# AC_Dimmer.net
KiCad netlist of a schematic drawn in Altium Designer
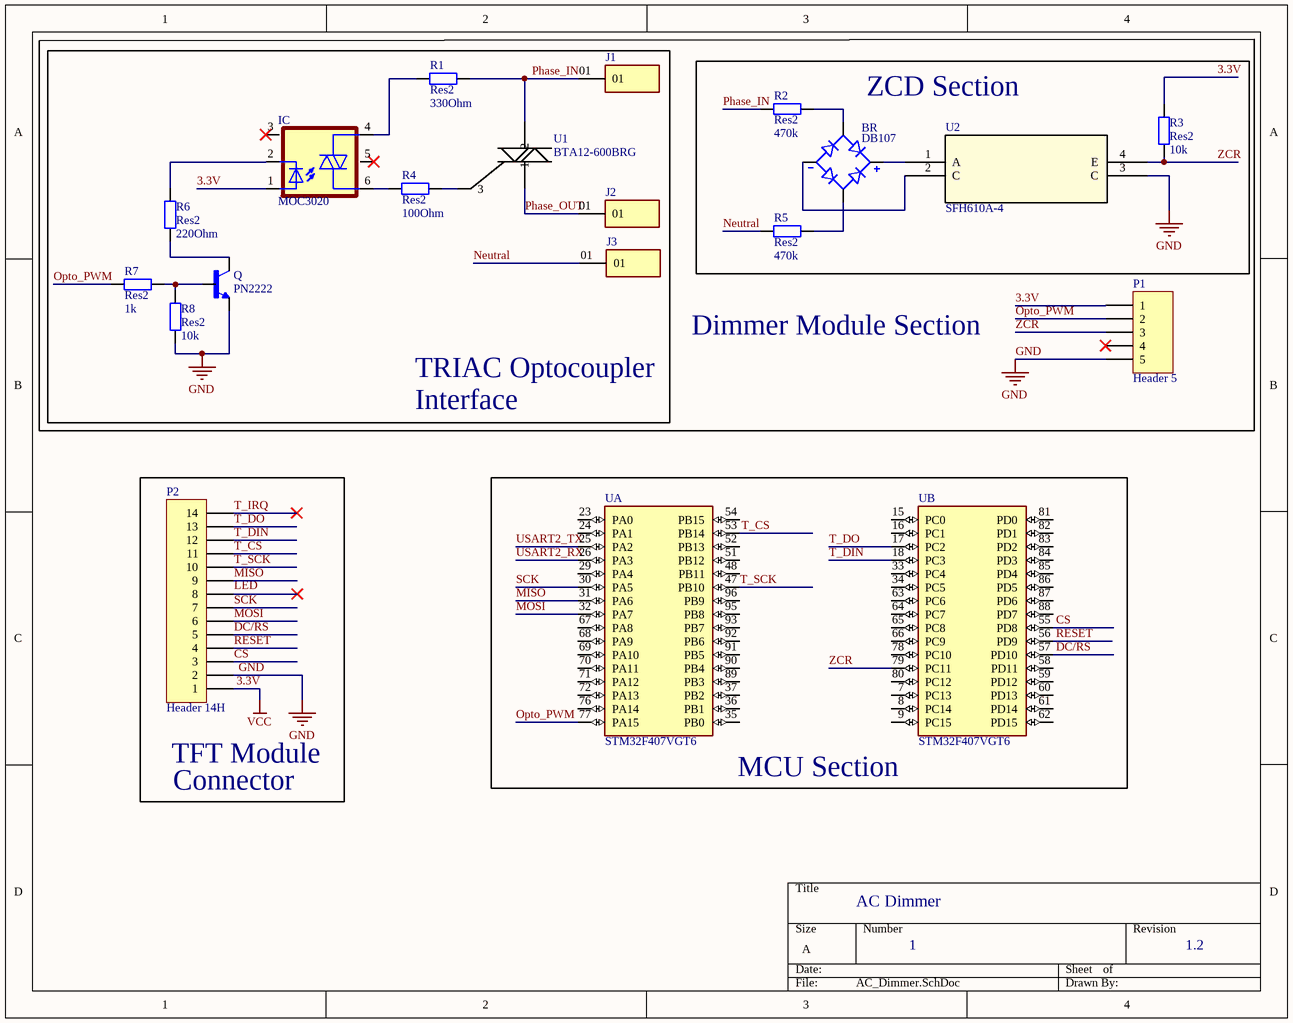
[diagram p0: AC_Dimmer.SchDoc]

(export (version "E")
  (design (tool "Eeschema 10.0.6"))
  (components
    (comp (ref "BR")
      (value "DB107")
      (footprint "DIP825W50P509L880H320Q4")
      (description "Bridge Rectifier Single Phase Standard 1kV Surface Mount DB-S")
      (fields (field (name "MF") "EIC Semiconductor"))
      (libsource (lib "DB107") (part "DB107"))
    )
    (comp (ref "IC")
      (value "MOC3020")
      (footprint "DIL06-A")
      (description "Optoisolator Triac Output 5300Vrms 1 Channel 6-DIP")
      (fields (field (name "MF") "ON Semiconductor"))
      (libsource (lib "MOC3020") (part "MOC3020"))
    )
    (comp (ref "J1")
      (value "MTMM-101-07-T-S-230")
      (footprint "SAMTEC_MTMM-101-07-T-S-230")
      (libsource (lib "MTMM-101-07-T-S-230") (part "MTMM-101-07-T-S-230"))
    )
    (comp (ref "J2")
      (value "MTMM-101-07-T-S-230")
      (footprint "SAMTEC_MTMM-101-07-T-S-230")
      (libsource (lib "MTMM-101-07-T-S-230") (part "MTMM-101-07-T-S-230"))
    )
    (comp (ref "J3")
      (value "MTMM-101-07-T-S-230")
      (footprint "SAMTEC_MTMM-101-07-T-S-230")
      (libsource (lib "MTMM-101-07-T-S-230") (part "MTMM-101-07-T-S-230"))
    )
    (comp (ref "P1")
      (value "Header 5")
      (footprint "HDR1X5")
      (description "Header, 5-Pin")
      (fields (field (name "PUBLISHER") "Altium Limited"))
      (libsource (lib "Miscellaneous Connectors") (part "Header 5"))
    )
    (comp (ref "P2")
      (value "Header 14H")
      (footprint "HDR1X14H")
      (description "Header, 14-Pin, Right Angle")
      (fields (field (name "PUBLISHER") "Altium Limited"))
      (libsource (lib "Miscellaneous Connectors") (part "Header 14H"))
    )
    (comp (ref "Q")
      (value "PN2222")
      (footprint "TO92")
      (description "Bipolar (BJT) Transistor NPN 40V 1A 300MHz 625mW Through Hole TO-92-3")
      (fields (field (name "MF") "ON Semiconductor"))
      (libsource (lib "PN2222") (part "PN2222"))
    )
    (comp (ref "R1")
      (value "Res2")
      (footprint "AXIAL-0.4")
      (description "Resistor")
      (fields (field (name "ALTIUM_VALUE") "330Ohm") (field (name "PUBLISHER") "Altium Limited"))
      (libsource (lib "") (part "Res2_1"))
    )
    (comp (ref "R2")
      (value "Res2")
      (footprint "AXIAL-0.4")
      (description "Resistor")
      (fields (field (name "ALTIUM_VALUE") "470k") (field (name "PUBLISHER") "Altium Limited"))
      (libsource (lib "") (part "Res2_2"))
    )
    (comp (ref "R3")
      (value "Res2")
      (footprint "AXIAL-0.4")
      (description "Resistor")
      (fields (field (name "ALTIUM_VALUE") "10k") (field (name "PUBLISHER") "Altium Limited"))
      (libsource (lib "Miscellaneous Devices") (part "Res2"))
    )
    (comp (ref "R4")
      (value "Res2")
      (footprint "AXIAL-0.4")
      (description "Resistor")
      (fields (field (name "ALTIUM_VALUE") "100Ohm") (field (name "PUBLISHER") "Altium Limited"))
      (libsource (lib "") (part "Res2_1"))
    )
    (comp (ref "R5")
      (value "Res2")
      (footprint "AXIAL-0.4")
      (description "Resistor")
      (fields (field (name "ALTIUM_VALUE") "470k") (field (name "PUBLISHER") "Altium Limited"))
      (libsource (lib "") (part "Res2_2"))
    )
    (comp (ref "R6")
      (value "Res2")
      (footprint "AXIAL-0.4")
      (description "Resistor")
      (fields (field (name "ALTIUM_VALUE") "220Ohm") (field (name "PUBLISHER") "Altium Limited"))
      (libsource (lib "Miscellaneous Devices") (part "Res2"))
    )
    (comp (ref "R7")
      (value "Res2")
      (footprint "AXIAL-0.4")
      (description "Resistor")
      (fields (field (name "ALTIUM_VALUE") "1k") (field (name "PUBLISHER") "Altium Limited"))
      (libsource (lib "") (part "Res2_1"))
    )
    (comp (ref "R8")
      (value "Res2")
      (footprint "AXIAL-0.4")
      (description "Resistor")
      (fields (field (name "ALTIUM_VALUE") "10k") (field (name "PUBLISHER") "Altium Limited"))
      (libsource (lib "Miscellaneous Devices") (part "Res2"))
    )
    (comp (ref "U")
      (value "STM32F407VGT6")
      (footprint "QFP50P1600X1600X160-100N")
      (description "ARMÂ® CortexÂ®-M4 STM32F4 Microcontroller IC 32-Bit 168MHz 1MB _1M x 8_ FLASH 100-LQFP _14x14_")
      (fields (field (name "MF") "STMicroelectronics"))
      (libsource (lib "STM32F407VGT6") (part "STM32F407VGT6"))
    )
    (comp (ref "U1")
      (value "BTA12-600BRG")
      (footprint "TO-220AB_STM")
      (description "No Description Available")
      (fields (field (name "COPYRIGHT") "Copyright (C) 2022 Ultra Librarian. All rights reserved."))
      (libsource (lib "BTA12-600BRG") (part "BTA12-600BRG"))
    )
    (comp (ref "U2")
      (value "SFH610A-4")
      (footprint "DIP-4_SFH610A_VIS")
      (description "No Description Available")
      (fields (field (name "COPYRIGHT") "Copyright (C) 2022 Ultra Librarian. All rights reserved."))
      (libsource (lib "SFH610A-4") (part "SFH610A-4"))
    )
  )
  (nets
    (net (code "1") (name "/CS") (class "Default")
      (node (ref "P2") (pin "3") (pinfunction "3_3") (pintype "passive"))
      (node (ref "U") (pin "55") (pinfunction "PD8_55") (pintype "bidirectional"))
    )
    (net (code "2") (name "/DC{slash}RS") (class "Default")
      (node (ref "P2") (pin "5") (pinfunction "5_5") (pintype "passive"))
      (node (ref "U") (pin "57") (pinfunction "PD10_57") (pintype "bidirectional"))
    )
    (net (code "4") (name "/MISO") (class "Default")
      (node (ref "P2") (pin "9") (pinfunction "9_9") (pintype "passive"))
      (node (ref "U") (pin "31") (pinfunction "PA6_31") (pintype "bidirectional"))
    )
    (net (code "5") (name "/MOSI") (class "Default")
      (node (ref "P2") (pin "6") (pinfunction "6_6") (pintype "passive"))
      (node (ref "U") (pin "32") (pinfunction "PA7_32") (pintype "bidirectional"))
    )
    (net (code "6") (name "/Neutral") (class "Default")
      (node (ref "J3") (pin "01") (pinfunction "01_01") (pintype "passive"))
      (node (ref "R5") (pin "1") (pinfunction "1_1") (pintype "passive"))
    )
    (net (code "7") (name "/Opto_PWM") (class "Default")
      (node (ref "P1") (pin "2") (pinfunction "2_2") (pintype "passive"))
      (node (ref "R7") (pin "2") (pinfunction "2_2") (pintype "passive"))
      (node (ref "U") (pin "77") (pinfunction "PA15_77") (pintype "bidirectional"))
    )
    (net (code "8") (name "/Phase_IN") (class "Default")
      (node (ref "J1") (pin "01") (pinfunction "01_01") (pintype "passive"))
      (node (ref "R1") (pin "1") (pinfunction "1_1") (pintype "passive"))
      (node (ref "R2") (pin "1") (pinfunction "1_1") (pintype "passive"))
      (node (ref "U1") (pin "2") (pinfunction "2_2") (pintype "passive"))
    )
    (net (code "9") (name "/Phase_OUT") (class "Default")
      (node (ref "J2") (pin "01") (pinfunction "01_01") (pintype "passive"))
      (node (ref "U1") (pin "1") (pinfunction "1_1") (pintype "passive"))
    )
    (net (code "10") (name "/RESET") (class "Default")
      (node (ref "P2") (pin "4") (pinfunction "4_4") (pintype "passive"))
      (node (ref "U") (pin "56") (pinfunction "PD9_56") (pintype "bidirectional"))
    )
    (net (code "11") (name "/SCK") (class "Default")
      (node (ref "P2") (pin "7") (pinfunction "7_7") (pintype "passive"))
      (node (ref "U") (pin "30") (pinfunction "PA5_30") (pintype "bidirectional"))
    )
    (net (code "12") (name "/T_CS") (class "Default")
      (node (ref "P2") (pin "11") (pinfunction "11_11") (pintype "passive"))
      (node (ref "U") (pin "53") (pinfunction "PB14_53") (pintype "bidirectional"))
    )
    (net (code "13") (name "/T_DIN") (class "Default")
      (node (ref "P2") (pin "12") (pinfunction "12_12") (pintype "passive"))
      (node (ref "U") (pin "18") (pinfunction "PC3_18") (pintype "bidirectional"))
    )
    (net (code "14") (name "/T_DO") (class "Default")
      (node (ref "P2") (pin "13") (pinfunction "13_13") (pintype "passive"))
      (node (ref "U") (pin "17") (pinfunction "PC2_17") (pintype "bidirectional"))
    )
    (net (code "15") (name "/T_IRQ") (class "Default")
      (node (ref "P2") (pin "14") (pinfunction "14_14") (pintype "passive+no_connect"))
    )
    (net (code "16") (name "/T_SCK") (class "Default")
      (node (ref "P2") (pin "10") (pinfunction "10_10") (pintype "passive"))
      (node (ref "U") (pin "47") (pinfunction "PB10_47") (pintype "bidirectional"))
    )
    (net (code "17") (name "/USART2_RX") (class "Default")
      (node (ref "U") (pin "26") (pinfunction "PA3_26") (pintype "bidirectional"))
    )
    (net (code "18") (name "/USART2_TX") (class "Default")
      (node (ref "U") (pin "25") (pinfunction "PA2_25") (pintype "bidirectional"))
    )
    (net (code "19") (name "/ZCR") (class "Default")
      (node (ref "P1") (pin "3") (pinfunction "3_3") (pintype "passive"))
      (node (ref "R3") (pin "2") (pinfunction "2_2") (pintype "passive"))
      (node (ref "U") (pin "79") (pinfunction "PC11_79") (pintype "bidirectional"))
      (node (ref "U2") (pin "4") (pinfunction "E_4") (pintype "passive"))
    )
    (net (code "20") (name "GND") (class "Default")
      (node (ref "P1") (pin "5") (pinfunction "5_5") (pintype "passive"))
      (node (ref "P2") (pin "2") (pinfunction "2_2") (pintype "passive"))
      (node (ref "Q") (pin "1") (pinfunction "E_1") (pintype "passive"))
      (node (ref "R8") (pin "2") (pinfunction "2_2") (pintype "passive"))
      (node (ref "U2") (pin "3") (pinfunction "C_3") (pintype "passive"))
    )
    (net (code "21") (name "Net-(BR-AC1)") (class "Default")
      (node (ref "BR") (pin "3") (pinfunction "AC1_3") (pintype "passive"))
      (node (ref "R5") (pin "2") (pinfunction "2_2") (pintype "passive"))
    )
    (net (code "22") (name "Net-(BR-AC2)") (class "Default")
      (node (ref "BR") (pin "4") (pinfunction "AC2_4") (pintype "passive"))
      (node (ref "R2") (pin "2") (pinfunction "2_2") (pintype "passive"))
    )
    (net (code "23") (name "Net-(BR-NEG)") (class "Default")
      (node (ref "BR") (pin "2") (pinfunction "NEG_2") (pintype "passive"))
      (node (ref "U2") (pin "2") (pinfunction "C_2") (pintype "passive"))
    )
    (net (code "24") (name "Net-(BR-POS)") (class "Default")
      (node (ref "BR") (pin "1") (pinfunction "POS_1") (pintype "passive"))
      (node (ref "U2") (pin "1") (pinfunction "A_1") (pintype "passive"))
    )
    (net (code "25") (name "Net-(IC-A1)") (class "Default")
      (node (ref "IC") (pin "4") (pinfunction "A1_4") (pintype "passive"))
      (node (ref "R1") (pin "2") (pinfunction "2_2") (pintype "passive"))
    )
    (net (code "26") (name "Net-(IC-A2)") (class "Default")
      (node (ref "IC") (pin "6") (pinfunction "A2_6") (pintype "passive"))
      (node (ref "R4") (pin "2") (pinfunction "2_2") (pintype "passive"))
    )
    (net (code "27") (name "Net-(IC-C)") (class "Default")
      (node (ref "IC") (pin "2") (pinfunction "C_2") (pintype "passive"))
      (node (ref "R6") (pin "1") (pinfunction "1_1") (pintype "passive"))
    )
    (net (code "28") (name "Net-(Q-B)") (class "Default")
      (node (ref "Q") (pin "2") (pinfunction "B_2") (pintype "passive"))
      (node (ref "R7") (pin "1") (pinfunction "1_1") (pintype "passive"))
      (node (ref "R8") (pin "1") (pinfunction "1_1") (pintype "passive"))
    )
    (net (code "29") (name "Net-(Q-C)") (class "Default")
      (node (ref "Q") (pin "3") (pinfunction "C_3") (pintype "passive"))
      (node (ref "R6") (pin "2") (pinfunction "2_2") (pintype "passive"))
    )
    (net (code "30") (name "Net-(R4-Pad1)") (class "Default")
      (node (ref "R4") (pin "1") (pinfunction "1_1") (pintype "passive"))
      (node (ref "U1") (pin "3") (pinfunction "3_3") (pintype "passive"))
    )
    (net (code "31") (name "VCC") (class "Default")
      (node (ref "IC") (pin "1") (pinfunction "A_1") (pintype "passive"))
      (node (ref "P1") (pin "1") (pinfunction "1_1") (pintype "passive"))
      (node (ref "P2") (pin "1") (pinfunction "1_1") (pintype "passive"))
      (node (ref "R3") (pin "1") (pinfunction "1_1") (pintype "passive"))
    )
    (net (code "32") (name "unconnected-(IC-P$1-Pad3)") (class "Default")
      (node (ref "IC") (pin "3") (pinfunction "P$1_3") (pintype "open_collector+no_connect"))
    )
    (net (code "33") (name "unconnected-(IC-P$2-Pad5)") (class "Default")
      (node (ref "IC") (pin "5") (pinfunction "P$2_5") (pintype "open_collector+no_connect"))
    )
    (net (code "34") (name "unconnected-(P1-Pad4)") (class "Default")
      (node (ref "P1") (pin "4") (pinfunction "4_4") (pintype "passive+no_connect"))
    )
    (net (code "35") (name "unconnected-(P2-Pad8)") (class "Default")
      (node (ref "P2") (pin "8") (pinfunction "8_8") (pintype "passive+no_connect"))
    )
    (net (code "36") (name "unconnected-(UA-PA0-Pad23)") (class "Default")
      (node (ref "U") (pin "23") (pinfunction "PA0_23") (pintype "bidirectional"))
    )
    (net (code "37") (name "unconnected-(UA-PA1-Pad24)") (class "Default")
      (node (ref "U") (pin "24") (pinfunction "PA1_24") (pintype "bidirectional"))
    )
    (net (code "38") (name "unconnected-(UA-PA4-Pad29)") (class "Default")
      (node (ref "U") (pin "29") (pinfunction "PA4_29") (pintype "bidirectional"))
    )
    (net (code "39") (name "unconnected-(UA-PA8-Pad67)") (class "Default")
      (node (ref "U") (pin "67") (pinfunction "PA8_67") (pintype "bidirectional"))
    )
    (net (code "40") (name "unconnected-(UA-PA9-Pad68)") (class "Default")
      (node (ref "U") (pin "68") (pinfunction "PA9_68") (pintype "bidirectional"))
    )
    (net (code "41") (name "unconnected-(UA-PA10-Pad69)") (class "Default")
      (node (ref "U") (pin "69") (pinfunction "PA10_69") (pintype "bidirectional"))
    )
    (net (code "42") (name "unconnected-(UA-PA11-Pad70)") (class "Default")
      (node (ref "U") (pin "70") (pinfunction "PA11_70") (pintype "bidirectional"))
    )
    (net (code "43") (name "unconnected-(UA-PA12-Pad71)") (class "Default")
      (node (ref "U") (pin "71") (pinfunction "PA12_71") (pintype "bidirectional"))
    )
    (net (code "44") (name "unconnected-(UA-PA13-Pad72)") (class "Default")
      (node (ref "U") (pin "72") (pinfunction "PA13_72") (pintype "bidirectional"))
    )
    (net (code "45") (name "unconnected-(UA-PA14-Pad76)") (class "Default")
      (node (ref "U") (pin "76") (pinfunction "PA14_76") (pintype "bidirectional"))
    )
    (net (code "46") (name "unconnected-(UA-PB0-Pad35)") (class "Default")
      (node (ref "U") (pin "35") (pinfunction "PB0_35") (pintype "bidirectional"))
    )
    (net (code "47") (name "unconnected-(UA-PB1-Pad36)") (class "Default")
      (node (ref "U") (pin "36") (pinfunction "PB1_36") (pintype "bidirectional"))
    )
    (net (code "48") (name "unconnected-(UA-PB2-Pad37)") (class "Default")
      (node (ref "U") (pin "37") (pinfunction "PB2_37") (pintype "bidirectional"))
    )
    (net (code "49") (name "unconnected-(UA-PB3-Pad89)") (class "Default")
      (node (ref "U") (pin "89") (pinfunction "PB3_89") (pintype "bidirectional"))
    )
    (net (code "50") (name "unconnected-(UA-PB4-Pad90)") (class "Default")
      (node (ref "U") (pin "90") (pinfunction "PB4_90") (pintype "bidirectional"))
    )
    (net (code "51") (name "unconnected-(UA-PB5-Pad91)") (class "Default")
      (node (ref "U") (pin "91") (pinfunction "PB5_91") (pintype "bidirectional"))
    )
    (net (code "52") (name "unconnected-(UA-PB6-Pad92)") (class "Default")
      (node (ref "U") (pin "92") (pinfunction "PB6_92") (pintype "bidirectional"))
    )
    (net (code "53") (name "unconnected-(UA-PB7-Pad93)") (class "Default")
      (node (ref "U") (pin "93") (pinfunction "PB7_93") (pintype "bidirectional"))
    )
    (net (code "54") (name "unconnected-(UA-PB8-Pad95)") (class "Default")
      (node (ref "U") (pin "95") (pinfunction "PB8_95") (pintype "bidirectional"))
    )
    (net (code "55") (name "unconnected-(UA-PB9-Pad96)") (class "Default")
      (node (ref "U") (pin "96") (pinfunction "PB9_96") (pintype "bidirectional"))
    )
    (net (code "56") (name "unconnected-(UA-PB11-Pad48)") (class "Default")
      (node (ref "U") (pin "48") (pinfunction "PB11_48") (pintype "bidirectional"))
    )
    (net (code "57") (name "unconnected-(UA-PB12-Pad51)") (class "Default")
      (node (ref "U") (pin "51") (pinfunction "PB12_51") (pintype "bidirectional"))
    )
    (net (code "58") (name "unconnected-(UA-PB13-Pad52)") (class "Default")
      (node (ref "U") (pin "52") (pinfunction "PB13_52") (pintype "bidirectional"))
    )
    (net (code "59") (name "unconnected-(UA-PB15-Pad54)") (class "Default")
      (node (ref "U") (pin "54") (pinfunction "PB15_54") (pintype "bidirectional"))
    )
    (net (code "60") (name "unconnected-(UB-PC0-Pad15)") (class "Default")
      (node (ref "U") (pin "15") (pinfunction "PC0_15") (pintype "bidirectional"))
    )
    (net (code "61") (name "unconnected-(UB-PC1-Pad16)") (class "Default")
      (node (ref "U") (pin "16") (pinfunction "PC1_16") (pintype "bidirectional"))
    )
    (net (code "62") (name "unconnected-(UB-PC4-Pad33)") (class "Default")
      (node (ref "U") (pin "33") (pinfunction "PC4_33") (pintype "bidirectional"))
    )
    (net (code "63") (name "unconnected-(UB-PC5-Pad34)") (class "Default")
      (node (ref "U") (pin "34") (pinfunction "PC5_34") (pintype "bidirectional"))
    )
    (net (code "64") (name "unconnected-(UB-PC6-Pad63)") (class "Default")
      (node (ref "U") (pin "63") (pinfunction "PC6_63") (pintype "bidirectional"))
    )
    (net (code "65") (name "unconnected-(UB-PC7-Pad64)") (class "Default")
      (node (ref "U") (pin "64") (pinfunction "PC7_64") (pintype "bidirectional"))
    )
    (net (code "66") (name "unconnected-(UB-PC8-Pad65)") (class "Default")
      (node (ref "U") (pin "65") (pinfunction "PC8_65") (pintype "bidirectional"))
    )
    (net (code "67") (name "unconnected-(UB-PC9-Pad66)") (class "Default")
      (node (ref "U") (pin "66") (pinfunction "PC9_66") (pintype "bidirectional"))
    )
    (net (code "68") (name "unconnected-(UB-PC10-Pad78)") (class "Default")
      (node (ref "U") (pin "78") (pinfunction "PC10_78") (pintype "bidirectional"))
    )
    (net (code "69") (name "unconnected-(UB-PC12-Pad80)") (class "Default")
      (node (ref "U") (pin "80") (pinfunction "PC12_80") (pintype "bidirectional"))
    )
    (net (code "70") (name "unconnected-(UB-PC13-Pad7)") (class "Default")
      (node (ref "U") (pin "7") (pinfunction "PC13_7") (pintype "bidirectional"))
    )
    (net (code "71") (name "unconnected-(UB-PC14-Pad8)") (class "Default")
      (node (ref "U") (pin "8") (pinfunction "PC14_8") (pintype "bidirectional"))
    )
    (net (code "72") (name "unconnected-(UB-PC15-Pad9)") (class "Default")
      (node (ref "U") (pin "9") (pinfunction "PC15_9") (pintype "bidirectional"))
    )
    (net (code "73") (name "unconnected-(UB-PD0-Pad81)") (class "Default")
      (node (ref "U") (pin "81") (pinfunction "PD0_81") (pintype "bidirectional"))
    )
    (net (code "74") (name "unconnected-(UB-PD1-Pad82)") (class "Default")
      (node (ref "U") (pin "82") (pinfunction "PD1_82") (pintype "bidirectional"))
    )
    (net (code "75") (name "unconnected-(UB-PD2-Pad83)") (class "Default")
      (node (ref "U") (pin "83") (pinfunction "PD2_83") (pintype "bidirectional"))
    )
    (net (code "76") (name "unconnected-(UB-PD3-Pad84)") (class "Default")
      (node (ref "U") (pin "84") (pinfunction "PD3_84") (pintype "bidirectional"))
    )
    (net (code "77") (name "unconnected-(UB-PD4-Pad85)") (class "Default")
      (node (ref "U") (pin "85") (pinfunction "PD4_85") (pintype "bidirectional"))
    )
    (net (code "78") (name "unconnected-(UB-PD5-Pad86)") (class "Default")
      (node (ref "U") (pin "86") (pinfunction "PD5_86") (pintype "bidirectional"))
    )
    (net (code "79") (name "unconnected-(UB-PD6-Pad87)") (class "Default")
      (node (ref "U") (pin "87") (pinfunction "PD6_87") (pintype "bidirectional"))
    )
    (net (code "80") (name "unconnected-(UB-PD7-Pad88)") (class "Default")
      (node (ref "U") (pin "88") (pinfunction "PD7_88") (pintype "bidirectional"))
    )
    (net (code "81") (name "unconnected-(UB-PD11-Pad58)") (class "Default")
      (node (ref "U") (pin "58") (pinfunction "PD11_58") (pintype "bidirectional"))
    )
    (net (code "82") (name "unconnected-(UB-PD12-Pad59)") (class "Default")
      (node (ref "U") (pin "59") (pinfunction "PD12_59") (pintype "bidirectional"))
    )
    (net (code "83") (name "unconnected-(UB-PD13-Pad60)") (class "Default")
      (node (ref "U") (pin "60") (pinfunction "PD13_60") (pintype "bidirectional"))
    )
    (net (code "84") (name "unconnected-(UB-PD14-Pad61)") (class "Default")
      (node (ref "U") (pin "61") (pinfunction "PD14_61") (pintype "bidirectional"))
    )
    (net (code "85") (name "unconnected-(UB-PD15-Pad62)") (class "Default")
      (node (ref "U") (pin "62") (pinfunction "PD15_62") (pintype "bidirectional"))
    )
  )
)
